# Safety_Loop.net
KiCad netlist of a schematic drawn in Altium Designer
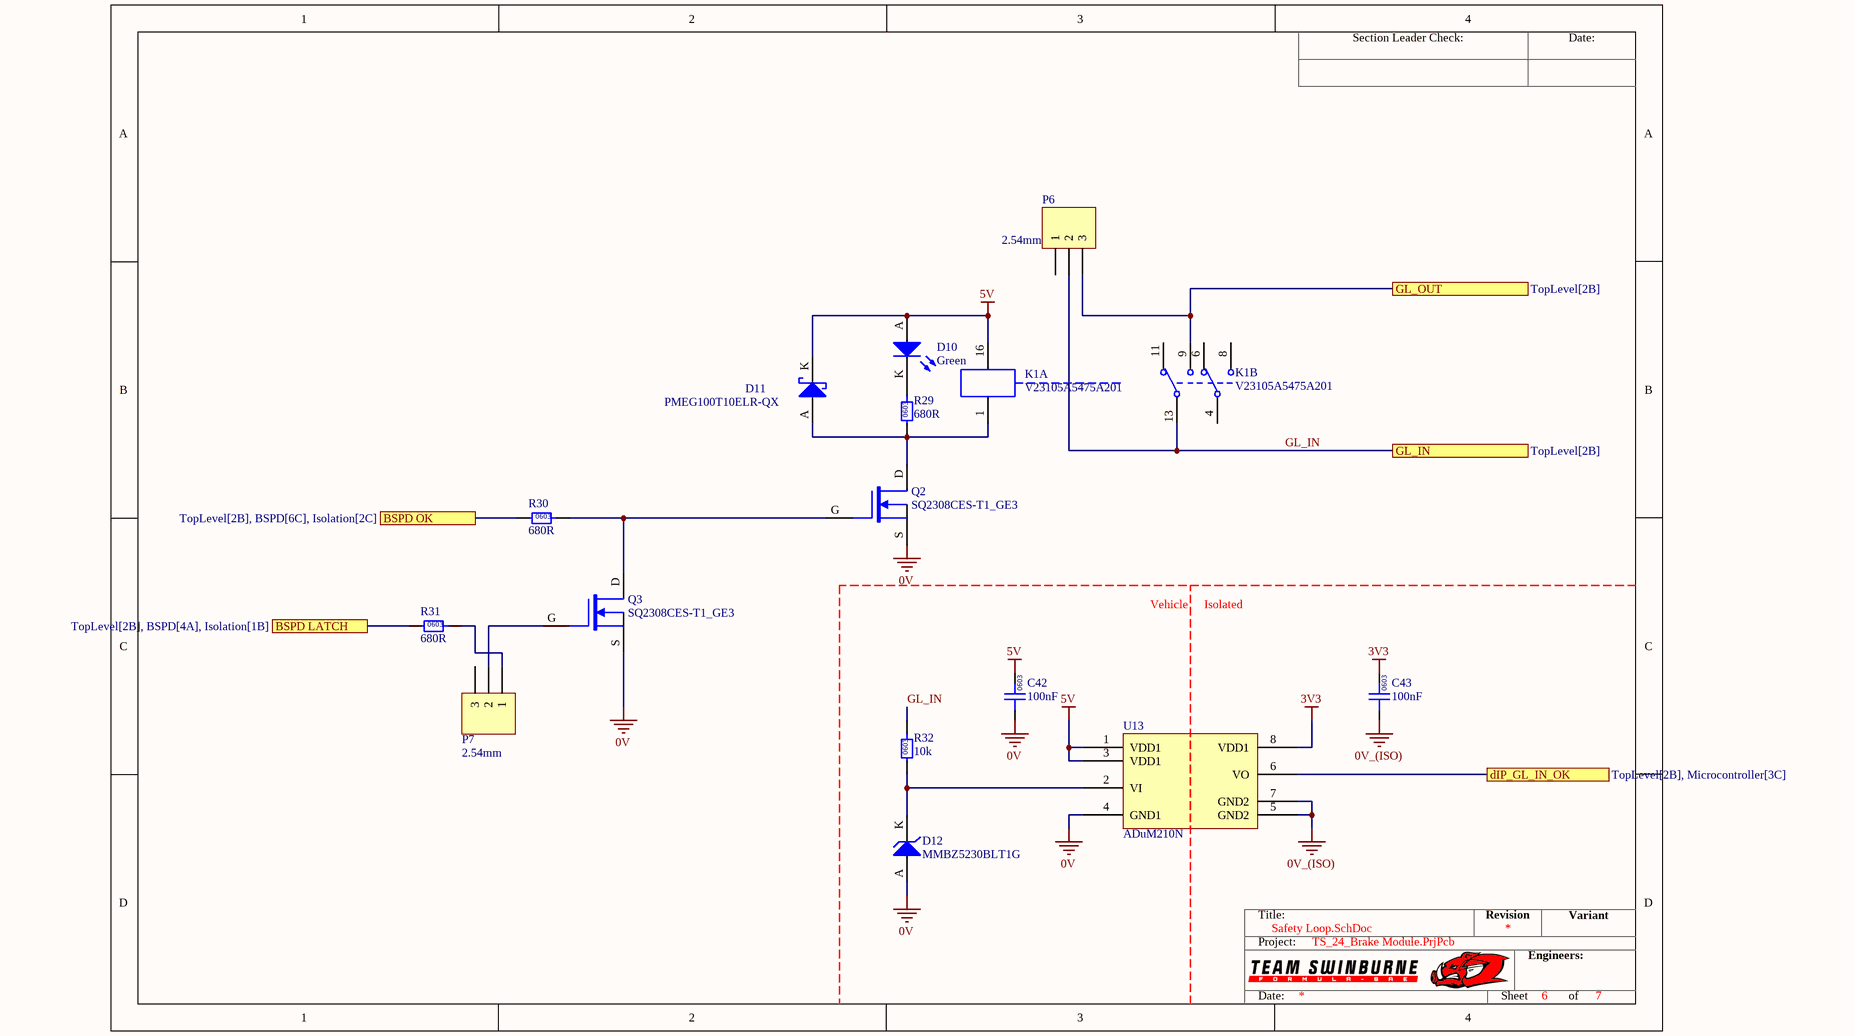
[diagram p0: Safety Loop.SchDoc]

(export (version "E")
  (design (tool "Eeschema 10.0.6"))
  (components
    (comp (ref "C42")
      (value "100nF")
      (footprint "0603")
      (fields
        (field (name "PART NUMBER") "GCM188L81H104KA57D")
        (field (name "MANUFACTURER") "muRata")
        (field (name "TOLERANCE") "±10%")
      )
      (libsource (lib "ts_standard_library") (part "Capacitor 0603"))
    )
    (comp (ref "C43")
      (value "100nF")
      (footprint "0603")
      (fields
        (field (name "PART NUMBER") "GCM188L81H104KA57D")
        (field (name "MANUFACTURER") "muRata")
        (field (name "TOLERANCE") "±10%")
      )
      (libsource (lib "ts_standard_library") (part "Capacitor 0603"))
    )
    (comp (ref "D10")
      (value "Green")
      (footprint "0805 LED")
      (description "Green LED Indication - Discrete 1.75V 0805 (2012 Metric)")
      (fields (field (name "PART NUMBER") "SML-210FTT86") (field (name "MANUFACTURER") "ROHM Semiconductor"))
      (libsource (lib "ts_standard_library") (part "LED"))
    )
    (comp (ref "D11")
      (value "PMEG100T10ELR-QX")
      (footprint "NXP SOD123W")
      (fields
        (field (name "MANUFACTURER") "Nexperia USA Inc.")
        (field (name "DIGIKEY PART NUMBER") "1727-PMEG100T10ELR-QXCT-ND")
      )
      (libsource (lib "ts_standard_library") (part "Diode (Schottky)"))
    )
    (comp (ref "D12")
      (value "MMBZ5230BLT1G")
      (footprint "NEXPERIA_SOT23")
      (fields
        (field (name "MANUFACTURER") "onsemi")
        (field (name "DIGIKEY PART NUMBER") "MMBZ5230BLT1GOSTR-ND")
      )
      (libsource (lib "ts_standard_library") (part "Zener Diode"))
    )
    (comp (ref "K1")
      (value "V23105A5475A201")
      (footprint "TI 2-DIL")
      (description "5V DPDT Relay 3A 220VDC")
      (fields (field (name "MANUFACTURER") "Axicom") (field (name "DIGIKEY PART NUMBER") "PB383-ND"))
      (libsource (lib "") (part "V23105A5475A201_1"))
    )
    (comp (ref "P6")
      (value "2.54mm")
      (footprint "TH 2.54mm Header 1x3")
      (fields (field (name "PART NUMBER") "TH 2.54mm Header 1x3") (field (name "CONTACT") "NA"))
      (libsource (lib "") (part "Header 1x3_1"))
    )
    (comp (ref "P7")
      (value "2.54mm")
      (footprint "TH 2.54mm Header 1x3")
      (fields (field (name "PART NUMBER") "TH 2.54mm Header 1x3") (field (name "CONTACT") "NA"))
      (libsource (lib "ts_standard_connectors") (part "Header 1x3"))
    )
    (comp (ref "Q2")
      (value "SQ2308CES-T1_GE3")
      (footprint "VSHY SOT-23-3")
      (description "MOSFET N-CH 60V 2.3A SOT23")
      (fields
        (field (name "MANUFACTURER") "Vishay Siliconix")
        (field (name "DIGIKEY PART NUMBER") "SQ2308CES-T1_GE3CT-ND")
        (field (name "PUBLISHER") "Altium Limited")
      )
      (libsource (lib "ts_standard_library") (part "MOSFET-N"))
    )
    (comp (ref "Q3")
      (value "SQ2308CES-T1_GE3")
      (footprint "VSHY SOT-23-3")
      (description "MOSFET N-CH 60V 2.3A SOT23")
      (fields
        (field (name "MANUFACTURER") "Vishay Siliconix")
        (field (name "DIGIKEY PART NUMBER") "SQ2308CES-T1_GE3CT-ND")
        (field (name "PUBLISHER") "Altium Limited")
      )
      (libsource (lib "ts_standard_library") (part "MOSFET-N"))
    )
    (comp (ref "R29")
      (value "680R")
      (footprint "0603")
      (fields
        (field (name "PART NUMBER") "RC0603JR-13680RL")
        (field (name "MANUFACTURER") "YAGEO")
        (field (name "TOLERANCE") "0.01")
      )
      (libsource (lib "ts_standard_library") (part "Resistor 0603"))
    )
    (comp (ref "R30")
      (value "680R")
      (footprint "0603")
      (fields
        (field (name "PART NUMBER") "RC0603JR-13680RL")
        (field (name "MANUFACTURER") "YAGEO")
        (field (name "TOLERANCE") "0.01")
      )
      (libsource (lib "ts_standard_library") (part "Resistor 0603"))
    )
    (comp (ref "R31")
      (value "680R")
      (footprint "0603")
      (fields
        (field (name "PART NUMBER") "RC0603JR-13680RL")
        (field (name "MANUFACTURER") "YAGEO")
        (field (name "TOLERANCE") "0.01")
      )
      (libsource (lib "ts_standard_library") (part "Resistor 0603"))
    )
    (comp (ref "R32")
      (value "10k")
      (footprint "0603")
      (fields
        (field (name "PART NUMBER") "RC0603FR-0710KL")
        (field (name "MANUFACTURER") "YAGEO")
        (field (name "TOLERANCE") "0.01")
      )
      (libsource (lib "ts_standard_library") (part "Resistor 0603"))
    )
    (comp (ref "U13")
      (value "ADuM210N")
      (footprint "AD-SOIC-8W")
      (description "DGTL ISO 5000VRMS 1CH GP 8SOIC")
      (fields
        (field (name "MANUFACTURER") "Analogue Devices")
        (field (name "DIGIKEY PART NUMBER") "ADUM210N1BRIZ-ND")
      )
      (libsource (lib "ts_standard_library") (part "ADuM210N"))
    )
  )
  (nets
    (net (code "1") (name "/BSPD LATCH") (class "Default")
      (node (ref "R31") (pin "1") (pinfunction "1_1") (pintype "passive"))
    )
    (net (code "2") (name "/BSPD OK") (class "Default")
      (node (ref "R30") (pin "1") (pinfunction "1_1") (pintype "passive"))
    )
    (net (code "3") (name "/GL_IN") (class "Default")
      (node (ref "K1") (pin "13") (pinfunction "13_13") (pintype "passive"))
      (node (ref "P6") (pin "2") (pinfunction "2_2") (pintype "passive"))
      (node (ref "R32") (pin "2") (pinfunction "2_2") (pintype "passive"))
    )
    (net (code "4") (name "/GL_OUT") (class "Default")
      (node (ref "K1") (pin "9") (pinfunction "9_9") (pintype "passive"))
      (node (ref "P6") (pin "3") (pinfunction "3_3") (pintype "passive"))
    )
    (net (code "5") (name "/dIP_GL_IN_OK") (class "Default")
      (node (ref "U13") (pin "6") (pinfunction "VO_6") (pintype "passive"))
    )
    (net (code "6") (name "0V") (class "Default")
      (node (ref "C42") (pin "1") (pinfunction "1_1") (pintype "passive"))
      (node (ref "D12") (pin "A") (pinfunction "A_A") (pintype "passive"))
      (node (ref "Q2") (pin "S") (pinfunction "S_S") (pintype "passive"))
      (node (ref "Q3") (pin "S") (pinfunction "S_S") (pintype "passive"))
      (node (ref "U13") (pin "4") (pinfunction "GND1_4") (pintype "passive"))
    )
    (net (code "7") (name "0V_(ISO)") (class "Default")
      (node (ref "C43") (pin "1") (pinfunction "1_1") (pintype "passive"))
      (node (ref "U13") (pin "5") (pinfunction "GND2_5") (pintype "passive"))
      (node (ref "U13") (pin "7") (pinfunction "GND2_7") (pintype "passive"))
    )
    (net (code "8") (name "3V3") (class "Default")
      (node (ref "C43") (pin "2") (pinfunction "2_2") (pintype "passive"))
      (node (ref "U13") (pin "8") (pinfunction "VDD1_8") (pintype "passive"))
    )
    (net (code "9") (name "5V") (class "Default")
      (node (ref "C42") (pin "2") (pinfunction "2_2") (pintype "passive"))
      (node (ref "D10") (pin "A") (pinfunction "A_A") (pintype "passive"))
      (node (ref "D11") (pin "K") (pinfunction "K_K") (pintype "passive"))
      (node (ref "K1") (pin "16") (pinfunction "16_16") (pintype "passive"))
      (node (ref "U13") (pin "1") (pinfunction "VDD1_1") (pintype "passive"))
      (node (ref "U13") (pin "3") (pinfunction "VDD1_3") (pintype "passive"))
    )
    (net (code "10") (name "Net-(D10-PadK)") (class "Default")
      (node (ref "D10") (pin "K") (pinfunction "K_K") (pintype "passive"))
      (node (ref "R29") (pin "2") (pinfunction "2_2") (pintype "passive"))
    )
    (net (code "11") (name "Net-(D11-PadA)") (class "Default")
      (node (ref "D11") (pin "A") (pinfunction "A_A") (pintype "passive"))
      (node (ref "K1") (pin "1") (pinfunction "1_1") (pintype "passive"))
      (node (ref "Q2") (pin "D") (pinfunction "D_D") (pintype "passive"))
      (node (ref "R29") (pin "1") (pinfunction "1_1") (pintype "passive"))
    )
    (net (code "12") (name "Net-(P7-Pad1)") (class "Default")
      (node (ref "P7") (pin "1") (pinfunction "1_1") (pintype "passive"))
      (node (ref "R31") (pin "2") (pinfunction "2_2") (pintype "passive"))
    )
    (net (code "13") (name "Net-(P7-Pad2)") (class "Default")
      (node (ref "P7") (pin "2") (pinfunction "2_2") (pintype "passive"))
      (node (ref "Q3") (pin "G") (pinfunction "G_G") (pintype "passive"))
    )
    (net (code "14") (name "Net-(Q2-PadG)") (class "Default")
      (node (ref "Q2") (pin "G") (pinfunction "G_G") (pintype "passive"))
      (node (ref "Q3") (pin "D") (pinfunction "D_D") (pintype "passive"))
      (node (ref "R30") (pin "2") (pinfunction "2_2") (pintype "passive"))
    )
    (net (code "15") (name "Net-(U13-VI)") (class "Default")
      (node (ref "D12") (pin "K") (pinfunction "K_K") (pintype "passive"))
      (node (ref "R32") (pin "1") (pinfunction "1_1") (pintype "passive"))
      (node (ref "U13") (pin "2") (pinfunction "VI_2") (pintype "passive"))
    )
    (net (code "16") (name "unconnected-(K1-Pad4)") (class "Default")
      (node (ref "K1") (pin "4") (pinfunction "4_4") (pintype "passive"))
    )
    (net (code "17") (name "unconnected-(K1-Pad6)") (class "Default")
      (node (ref "K1") (pin "6") (pinfunction "6_6") (pintype "passive"))
    )
    (net (code "18") (name "unconnected-(K1-Pad8)") (class "Default")
      (node (ref "K1") (pin "8") (pinfunction "8_8") (pintype "passive"))
    )
    (net (code "19") (name "unconnected-(K1-Pad11)") (class "Default")
      (node (ref "K1") (pin "11") (pinfunction "11_11") (pintype "passive"))
    )
    (net (code "20") (name "unconnected-(P6-Pad1)") (class "Default")
      (node (ref "P6") (pin "1") (pinfunction "1_1") (pintype "passive"))
    )
    (net (code "21") (name "unconnected-(P7-Pad3)") (class "Default")
      (node (ref "P7") (pin "3") (pinfunction "3_3") (pintype "passive"))
    )
  )
)
